# NusbioMCU.net
KiCad netlist of a schematic drawn in EAGLE
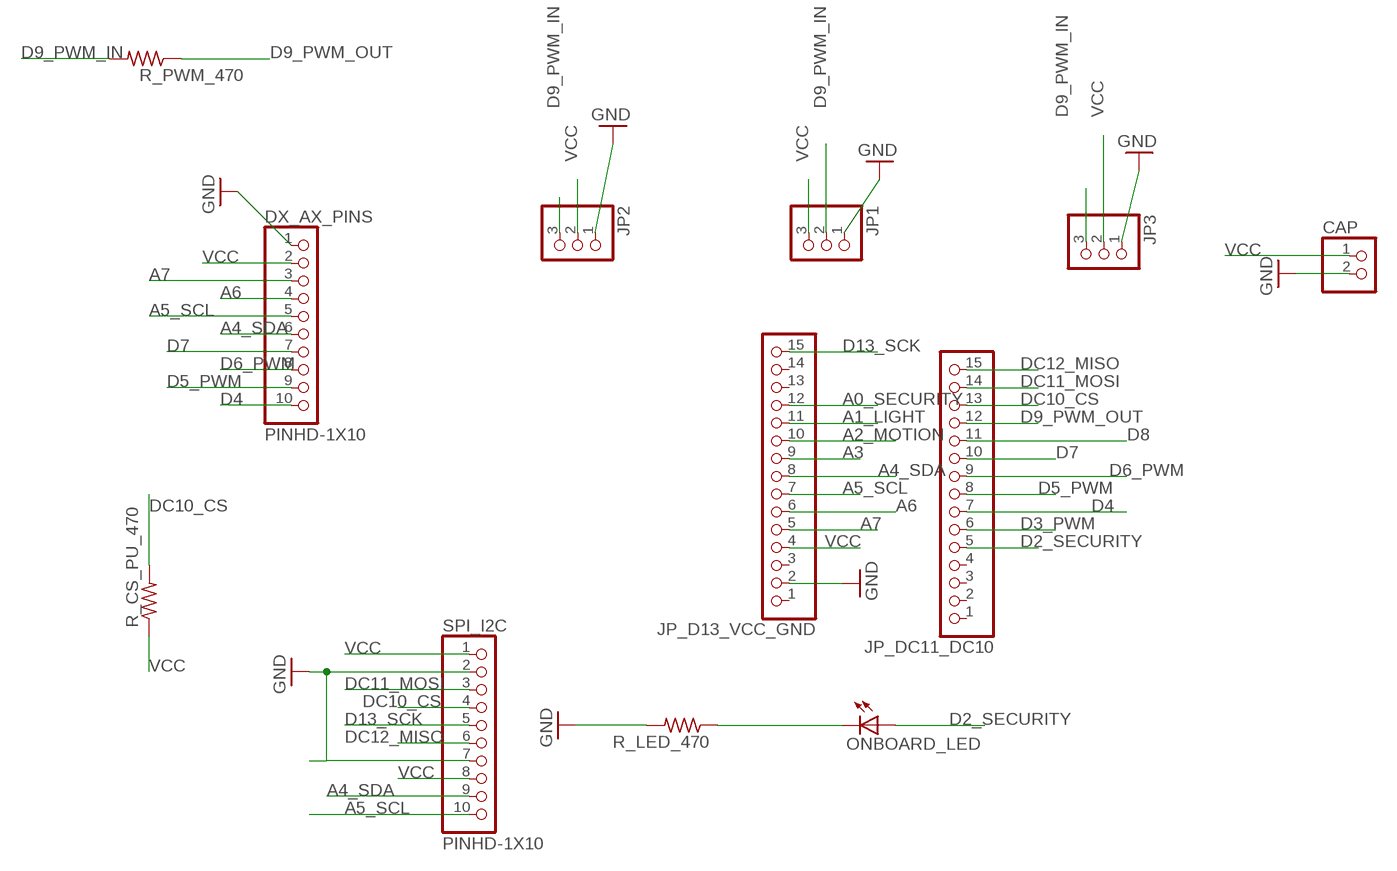
[diagram p0: schematic, sheet 1]

(export (version "E")
  (design (tool "Eeschema 10.0.6"))
  (components
    (comp (ref "CAP")
      (value "PINHD-1X2")
      (footprint "eagle-import:1X02")
      (libsource (lib "eagle-import") (part "PINHD-1X2"))
    )
    (comp (ref "DX_AX_PINS")
      (value "PINHD-1X10")
      (footprint "eagle-import:1X10-BIG")
      (libsource (lib "eagle-import") (part "PINHD-1X10"))
    )
    (comp (ref "JP1")
      (value "PINHD-1X3")
      (footprint "eagle-import:1X03")
      (libsource (lib "eagle-import") (part "PINHD-1X3"))
    )
    (comp (ref "JP2")
      (value "PINHD-1X3")
      (footprint "eagle-import:1X03")
      (libsource (lib "eagle-import") (part "PINHD-1X3"))
    )
    (comp (ref "JP3")
      (value "PINHD-1X3")
      (footprint "eagle-import:1X03")
      (libsource (lib "eagle-import") (part "PINHD-1X3"))
    )
    (comp (ref "JP_D13_VCC_GND")
      (value "PINHD-1X15")
      (footprint "eagle-import:1X15")
      (libsource (lib "eagle-import") (part "PINHD-1X15"))
    )
    (comp (ref "JP_DC11_DC10")
      (value "PINHD-1X15")
      (footprint "eagle-import:1X15")
      (libsource (lib "eagle-import") (part "PINHD-1X15"))
    )
    (comp (ref "ONBOARD_LED")
      (value "LEDSMT1206")
      (footprint "eagle-import:1206")
      (libsource (lib "eagle-import") (part "LEDSMT1206"))
    )
    (comp (ref "R_CS_PU_470")
      (value "R-US_R1206")
      (footprint "eagle-import:R1206")
      (libsource (lib "eagle-import") (part "R-US_R1206"))
    )
    (comp (ref "R_LED_470")
      (value "R-US_R1206")
      (footprint "eagle-import:R1206")
      (libsource (lib "eagle-import") (part "R-US_R1206"))
    )
    (comp (ref "R_PWM_470")
      (value "R-US_R1206")
      (footprint "eagle-import:R1206")
      (libsource (lib "eagle-import") (part "R-US_R1206"))
    )
    (comp (ref "SPI_I2C")
      (value "PINHD-1X10")
      (footprint "eagle-import:1X10-BIG")
      (libsource (lib "eagle-import") (part "PINHD-1X10"))
    )
  )
  (nets
    (net (code "1") (name "/A0_SECURITY") (class "Default")
      (node (ref "JP_D13_VCC_GND") (pin "12") (pinfunction "12_12") (pintype "passive"))
    )
    (net (code "2") (name "/A1_LIGHT") (class "Default")
      (node (ref "JP_D13_VCC_GND") (pin "11") (pinfunction "11_11") (pintype "passive"))
    )
    (net (code "3") (name "/A2_MOTION") (class "Default")
      (node (ref "JP_D13_VCC_GND") (pin "10") (pinfunction "10_10") (pintype "passive"))
    )
    (net (code "4") (name "/A3") (class "Default")
      (node (ref "JP_D13_VCC_GND") (pin "9") (pinfunction "9_9") (pintype "passive"))
    )
    (net (code "5") (name "/A4_SDA") (class "Default")
      (node (ref "DX_AX_PINS") (pin "6") (pinfunction "6_6") (pintype "passive"))
      (node (ref "JP_D13_VCC_GND") (pin "8") (pinfunction "8_8") (pintype "passive"))
      (node (ref "SPI_I2C") (pin "9") (pinfunction "9_9") (pintype "passive"))
    )
    (net (code "6") (name "/A5_SCL") (class "Default")
      (node (ref "DX_AX_PINS") (pin "5") (pinfunction "5_5") (pintype "passive"))
      (node (ref "JP_D13_VCC_GND") (pin "7") (pinfunction "7_7") (pintype "passive"))
      (node (ref "SPI_I2C") (pin "10") (pinfunction "10_10") (pintype "passive"))
    )
    (net (code "7") (name "/A6") (class "Default")
      (node (ref "DX_AX_PINS") (pin "4") (pinfunction "4_4") (pintype "passive"))
      (node (ref "JP_D13_VCC_GND") (pin "6") (pinfunction "6_6") (pintype "passive"))
    )
    (net (code "8") (name "/A7") (class "Default")
      (node (ref "DX_AX_PINS") (pin "3") (pinfunction "3_3") (pintype "passive"))
      (node (ref "JP_D13_VCC_GND") (pin "5") (pinfunction "5_5") (pintype "passive"))
    )
    (net (code "9") (name "/D2_SECURITY") (class "Default")
      (node (ref "JP_DC11_DC10") (pin "5") (pinfunction "5_5") (pintype "passive"))
      (node (ref "ONBOARD_LED") (pin "A") (pinfunction "A_A") (pintype "passive"))
    )
    (net (code "10") (name "/D3_PWM") (class "Default")
      (node (ref "JP_DC11_DC10") (pin "6") (pinfunction "6_6") (pintype "passive"))
    )
    (net (code "11") (name "/D4") (class "Default")
      (node (ref "DX_AX_PINS") (pin "10") (pinfunction "10_10") (pintype "passive"))
      (node (ref "JP_DC11_DC10") (pin "7") (pinfunction "7_7") (pintype "passive"))
    )
    (net (code "12") (name "/D5_PWM") (class "Default")
      (node (ref "DX_AX_PINS") (pin "9") (pinfunction "9_9") (pintype "passive"))
      (node (ref "JP_DC11_DC10") (pin "8") (pinfunction "8_8") (pintype "passive"))
    )
    (net (code "13") (name "/D6_PWM") (class "Default")
      (node (ref "DX_AX_PINS") (pin "8") (pinfunction "8_8") (pintype "passive"))
      (node (ref "JP_DC11_DC10") (pin "9") (pinfunction "9_9") (pintype "passive"))
    )
    (net (code "14") (name "/D7") (class "Default")
      (node (ref "DX_AX_PINS") (pin "7") (pinfunction "7_7") (pintype "passive"))
      (node (ref "JP_DC11_DC10") (pin "10") (pinfunction "10_10") (pintype "passive"))
    )
    (net (code "15") (name "/D8") (class "Default")
      (node (ref "JP_DC11_DC10") (pin "11") (pinfunction "11_11") (pintype "passive"))
    )
    (net (code "16") (name "/D9_PWM_IN") (class "Default")
      (node (ref "JP1") (pin "2") (pinfunction "2_2") (pintype "passive"))
      (node (ref "JP2") (pin "3") (pinfunction "3_3") (pintype "passive"))
      (node (ref "JP3") (pin "3") (pinfunction "3_3") (pintype "passive"))
      (node (ref "R_PWM_470") (pin "2") (pinfunction "2_2") (pintype "passive"))
    )
    (net (code "17") (name "/D9_PWM_OUT") (class "Default")
      (node (ref "JP_DC11_DC10") (pin "12") (pinfunction "12_12") (pintype "passive"))
      (node (ref "R_PWM_470") (pin "1") (pinfunction "1_1") (pintype "passive"))
    )
    (net (code "18") (name "/D13_SCK") (class "Default")
      (node (ref "JP_D13_VCC_GND") (pin "15") (pinfunction "15_15") (pintype "passive"))
      (node (ref "SPI_I2C") (pin "5") (pinfunction "5_5") (pintype "passive"))
    )
    (net (code "19") (name "/DC10_CS") (class "Default")
      (node (ref "JP_DC11_DC10") (pin "13") (pinfunction "13_13") (pintype "passive"))
      (node (ref "R_CS_PU_470") (pin "2") (pinfunction "2_2") (pintype "passive"))
      (node (ref "SPI_I2C") (pin "4") (pinfunction "4_4") (pintype "passive"))
    )
    (net (code "20") (name "/DC11_MOSI") (class "Default")
      (node (ref "JP_DC11_DC10") (pin "14") (pinfunction "14_14") (pintype "passive"))
      (node (ref "SPI_I2C") (pin "3") (pinfunction "3_3") (pintype "passive"))
    )
    (net (code "21") (name "/DC12_MISO") (class "Default")
      (node (ref "JP_DC11_DC10") (pin "15") (pinfunction "15_15") (pintype "passive"))
      (node (ref "SPI_I2C") (pin "6") (pinfunction "6_6") (pintype "passive"))
    )
    (net (code "22") (name "/VCC") (class "Default")
      (node (ref "CAP") (pin "1") (pinfunction "1_1") (pintype "passive"))
      (node (ref "DX_AX_PINS") (pin "2") (pinfunction "2_2") (pintype "passive"))
      (node (ref "JP1") (pin "3") (pinfunction "3_3") (pintype "passive"))
      (node (ref "JP2") (pin "2") (pinfunction "2_2") (pintype "passive"))
      (node (ref "JP3") (pin "2") (pinfunction "2_2") (pintype "passive"))
      (node (ref "JP_D13_VCC_GND") (pin "4") (pinfunction "4_4") (pintype "passive"))
      (node (ref "R_CS_PU_470") (pin "1") (pinfunction "1_1") (pintype "passive"))
      (node (ref "SPI_I2C") (pin "1") (pinfunction "1_1") (pintype "passive"))
      (node (ref "SPI_I2C") (pin "8") (pinfunction "8_8") (pintype "passive"))
    )
    (net (code "23") (name "GND") (class "Default")
      (node (ref "CAP") (pin "2") (pinfunction "2_2") (pintype "passive"))
      (node (ref "DX_AX_PINS") (pin "1") (pinfunction "1_1") (pintype "passive"))
      (node (ref "JP1") (pin "1") (pinfunction "1_1") (pintype "passive"))
      (node (ref "JP2") (pin "1") (pinfunction "1_1") (pintype "passive"))
      (node (ref "JP3") (pin "1") (pinfunction "1_1") (pintype "passive"))
      (node (ref "JP_D13_VCC_GND") (pin "2") (pinfunction "2_2") (pintype "passive"))
      (node (ref "R_LED_470") (pin "2") (pinfunction "2_2") (pintype "passive"))
      (node (ref "SPI_I2C") (pin "2") (pinfunction "2_2") (pintype "passive"))
      (node (ref "SPI_I2C") (pin "7") (pinfunction "7_7") (pintype "passive"))
    )
    (net (code "24") (name "Net-(ONBOARD_LED-PadC)") (class "Default")
      (node (ref "ONBOARD_LED") (pin "C") (pinfunction "C_C") (pintype "passive"))
      (node (ref "R_LED_470") (pin "1") (pinfunction "1_1") (pintype "passive"))
    )
    (net (code "25") (name "unconnected-(JP_D13_VCC_GND-Pad1)") (class "Default")
      (node (ref "JP_D13_VCC_GND") (pin "1") (pinfunction "1_1") (pintype "passive"))
    )
    (net (code "26") (name "unconnected-(JP_D13_VCC_GND-Pad3)") (class "Default")
      (node (ref "JP_D13_VCC_GND") (pin "3") (pinfunction "3_3") (pintype "passive"))
    )
    (net (code "27") (name "unconnected-(JP_D13_VCC_GND-Pad13)") (class "Default")
      (node (ref "JP_D13_VCC_GND") (pin "13") (pinfunction "13_13") (pintype "passive"))
    )
    (net (code "28") (name "unconnected-(JP_D13_VCC_GND-Pad14)") (class "Default")
      (node (ref "JP_D13_VCC_GND") (pin "14") (pinfunction "14_14") (pintype "passive"))
    )
    (net (code "29") (name "unconnected-(JP_DC11_DC10-Pad1)") (class "Default")
      (node (ref "JP_DC11_DC10") (pin "1") (pinfunction "1_1") (pintype "passive"))
    )
    (net (code "30") (name "unconnected-(JP_DC11_DC10-Pad2)") (class "Default")
      (node (ref "JP_DC11_DC10") (pin "2") (pinfunction "2_2") (pintype "passive"))
    )
    (net (code "31") (name "unconnected-(JP_DC11_DC10-Pad3)") (class "Default")
      (node (ref "JP_DC11_DC10") (pin "3") (pinfunction "3_3") (pintype "passive"))
    )
    (net (code "32") (name "unconnected-(JP_DC11_DC10-Pad4)") (class "Default")
      (node (ref "JP_DC11_DC10") (pin "4") (pinfunction "4_4") (pintype "passive"))
    )
  )
)
